# LICL_Diff.net
KiCad netlist of a schematic drawn in EAGLE
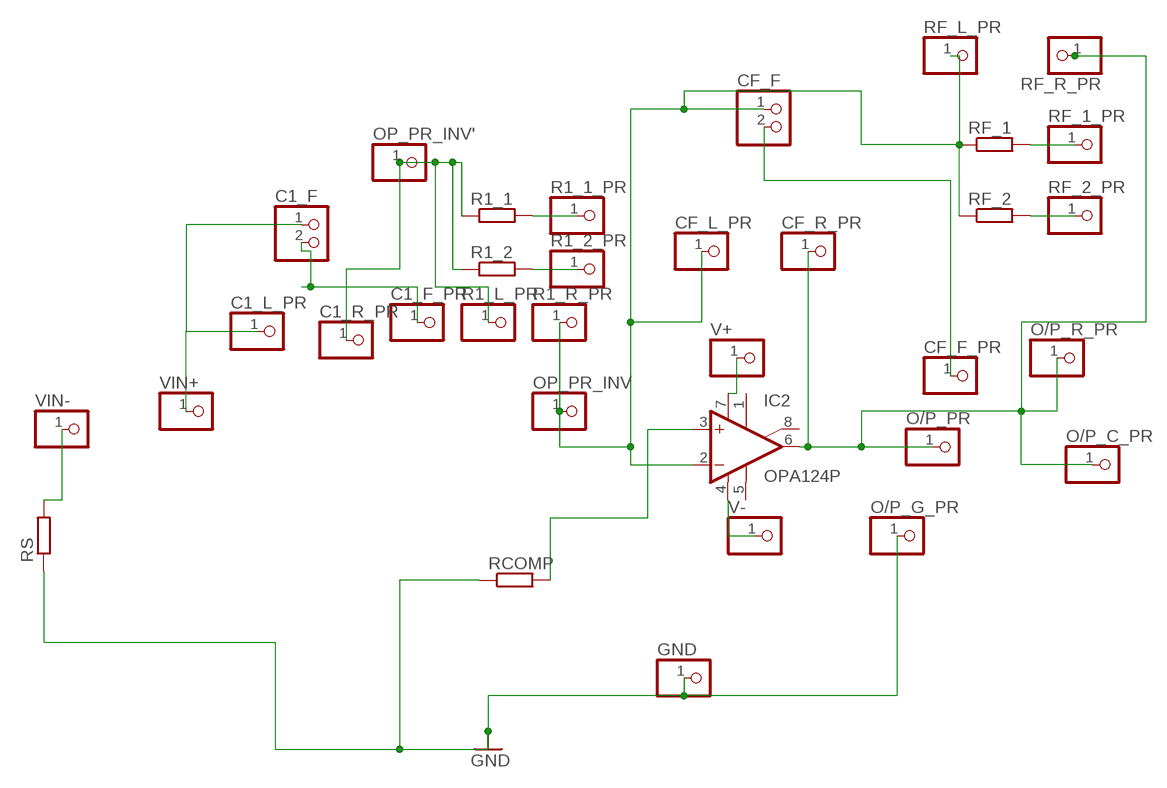
[diagram p0: schematic, sheet 1]

(export (version "E")
  (design (tool "Eeschema 10.0.6"))
  (components
    (comp (ref "C1_F")
      (value "PINHD-1X2")
      (footprint "eagle-import:1X02")
      (libsource (lib "eagle-import") (part "PINHD-1X2"))
    )
    (comp (ref "C1_F_PR")
      (value "PINHD-1X1")
      (footprint "eagle-import:1X01")
      (libsource (lib "eagle-import") (part "PINHD-1X1"))
    )
    (comp (ref "C1_L_PR")
      (value "PINHD-1X1")
      (footprint "eagle-import:1X01")
      (libsource (lib "eagle-import") (part "PINHD-1X1"))
    )
    (comp (ref "C1_R_PR")
      (value "PINHD-1X1")
      (footprint "eagle-import:1X01")
      (libsource (lib "eagle-import") (part "PINHD-1X1"))
    )
    (comp (ref "CF_F")
      (value "PINHD-1X2")
      (footprint "eagle-import:1X02")
      (libsource (lib "eagle-import") (part "PINHD-1X2"))
    )
    (comp (ref "CF_F_PR")
      (value "PINHD-1X1")
      (footprint "eagle-import:1X01")
      (libsource (lib "eagle-import") (part "PINHD-1X1"))
    )
    (comp (ref "CF_L_PR")
      (value "PINHD-1X1")
      (footprint "eagle-import:1X01")
      (libsource (lib "eagle-import") (part "PINHD-1X1"))
    )
    (comp (ref "CF_R_PR")
      (value "PINHD-1X1")
      (footprint "eagle-import:1X01")
      (libsource (lib "eagle-import") (part "PINHD-1X1"))
    )
    (comp (ref "GND")
      (value "PINHD-1X1")
      (footprint "eagle-import:1X01")
      (libsource (lib "eagle-import") (part "PINHD-1X1"))
    )
    (comp (ref "IC2")
      (value "OPA124P")
      (footprint "eagle-import:DIL08")
      (libsource (lib "eagle-import") (part "OPA124P"))
    )
    (comp (ref "O/P_C_PR")
      (value "PINHD-1X1")
      (footprint "eagle-import:1X01")
      (libsource (lib "eagle-import") (part "PINHD-1X1"))
    )
    (comp (ref "O/P_G_PR")
      (value "PINHD-1X1")
      (footprint "eagle-import:1X01")
      (libsource (lib "eagle-import") (part "PINHD-1X1"))
    )
    (comp (ref "O/P_PR")
      (value "PINHD-1X1")
      (footprint "eagle-import:1X01")
      (libsource (lib "eagle-import") (part "PINHD-1X1"))
    )
    (comp (ref "O/P_R_PR")
      (value "PINHD-1X1")
      (footprint "eagle-import:1X01")
      (libsource (lib "eagle-import") (part "PINHD-1X1"))
    )
    (comp (ref "OP_PR_INV")
      (value "PINHD-1X1")
      (footprint "eagle-import:1X01")
      (libsource (lib "eagle-import") (part "PINHD-1X1"))
    )
    (comp (ref "OP_PR_INV'")
      (value "PINHD-1X1")
      (footprint "eagle-import:1X01")
      (libsource (lib "eagle-import") (part "PINHD-1X1"))
    )
    (comp (ref "R1_1")
      (value "R-EU_0207/10")
      (footprint "eagle-import:0207_10")
      (libsource (lib "eagle-import") (part "R-EU_0207/10"))
    )
    (comp (ref "R1_1_PR")
      (value "PINHD-1X1")
      (footprint "eagle-import:1X01")
      (libsource (lib "eagle-import") (part "PINHD-1X1"))
    )
    (comp (ref "R1_2")
      (value "R-EU_0207/10")
      (footprint "eagle-import:0207_10")
      (libsource (lib "eagle-import") (part "R-EU_0207/10"))
    )
    (comp (ref "R1_2_PR")
      (value "PINHD-1X1")
      (footprint "eagle-import:1X01")
      (libsource (lib "eagle-import") (part "PINHD-1X1"))
    )
    (comp (ref "R1_L_PR")
      (value "PINHD-1X1")
      (footprint "eagle-import:1X01")
      (libsource (lib "eagle-import") (part "PINHD-1X1"))
    )
    (comp (ref "R1_R_PR")
      (value "PINHD-1X1")
      (footprint "eagle-import:1X01")
      (libsource (lib "eagle-import") (part "PINHD-1X1"))
    )
    (comp (ref "RCOMP")
      (value "R-EU_0207/10")
      (footprint "eagle-import:0207_10")
      (libsource (lib "eagle-import") (part "R-EU_0207/10"))
    )
    (comp (ref "RF_1")
      (value "R-EU_0207/10")
      (footprint "eagle-import:0207_10")
      (libsource (lib "eagle-import") (part "R-EU_0207/10"))
    )
    (comp (ref "RF_1_PR")
      (value "PINHD-1X1")
      (footprint "eagle-import:1X01")
      (libsource (lib "eagle-import") (part "PINHD-1X1"))
    )
    (comp (ref "RF_2")
      (value "R-EU_0207/10")
      (footprint "eagle-import:0207_10")
      (libsource (lib "eagle-import") (part "R-EU_0207/10"))
    )
    (comp (ref "RF_2_PR")
      (value "PINHD-1X1")
      (footprint "eagle-import:1X01")
      (libsource (lib "eagle-import") (part "PINHD-1X1"))
    )
    (comp (ref "RF_L_PR")
      (value "PINHD-1X1")
      (footprint "eagle-import:1X01")
      (libsource (lib "eagle-import") (part "PINHD-1X1"))
    )
    (comp (ref "RF_R_PR")
      (value "PINHD-1X1")
      (footprint "eagle-import:1X01")
      (libsource (lib "eagle-import") (part "PINHD-1X1"))
    )
    (comp (ref "RS")
      (value "R-EU_0207/10")
      (footprint "eagle-import:0207_10")
      (libsource (lib "eagle-import") (part "R-EU_0207/10"))
    )
    (comp (ref "V+")
      (value "PINHD-1X1")
      (footprint "eagle-import:1X01")
      (libsource (lib "eagle-import") (part "PINHD-1X1"))
    )
    (comp (ref "V-")
      (value "PINHD-1X1")
      (footprint "eagle-import:1X01")
      (libsource (lib "eagle-import") (part "PINHD-1X1"))
    )
    (comp (ref "VIN+")
      (value "PINHD-1X1")
      (footprint "eagle-import:1X01")
      (libsource (lib "eagle-import") (part "PINHD-1X1"))
    )
    (comp (ref "VIN-")
      (value "PINHD-1X1")
      (footprint "eagle-import:1X01")
      (libsource (lib "eagle-import") (part "PINHD-1X1"))
    )
  )
  (nets
    (net (code "1") (name "GND") (class "Default")
      (node (ref "GND") (pin "1") (pinfunction "1_1") (pintype "passive"))
      (node (ref "O/P_G_PR") (pin "1") (pinfunction "1_1") (pintype "passive"))
      (node (ref "RCOMP") (pin "1") (pinfunction "1_1") (pintype "passive"))
      (node (ref "RS") (pin "1") (pinfunction "1_1") (pintype "passive"))
    )
    (net (code "2") (name "Net-(C1_F-Pad1)") (class "Default")
      (node (ref "C1_F") (pin "1") (pinfunction "1_1") (pintype "passive"))
      (node (ref "C1_L_PR") (pin "1") (pinfunction "1_1") (pintype "passive"))
      (node (ref "VIN+") (pin "1") (pinfunction "1_1") (pintype "passive"))
    )
    (net (code "3") (name "Net-(C1_F-Pad2)") (class "Default")
      (node (ref "C1_F") (pin "2") (pinfunction "2_2") (pintype "passive"))
      (node (ref "C1_F_PR") (pin "1") (pinfunction "1_1") (pintype "passive"))
    )
    (net (code "4") (name "Net-(C1_R_PR-Pad1)") (class "Default")
      (node (ref "C1_R_PR") (pin "1") (pinfunction "1_1") (pintype "passive"))
      (node (ref "OP_PR_INV'") (pin "1") (pinfunction "1_1") (pintype "passive"))
      (node (ref "R1_1") (pin "1") (pinfunction "1_1") (pintype "passive"))
      (node (ref "R1_2") (pin "1") (pinfunction "1_1") (pintype "passive"))
      (node (ref "R1_L_PR") (pin "1") (pinfunction "1_1") (pintype "passive"))
    )
    (net (code "5") (name "Net-(CF_F-Pad2)") (class "Default")
      (node (ref "CF_F") (pin "2") (pinfunction "2_2") (pintype "passive"))
      (node (ref "CF_F_PR") (pin "1") (pinfunction "1_1") (pintype "passive"))
    )
    (net (code "6") (name "Net-(IC2-+IN)") (class "Default")
      (node (ref "IC2") (pin "3") (pinfunction "+IN_3") (pintype "input"))
      (node (ref "RCOMP") (pin "2") (pinfunction "2_2") (pintype "passive"))
    )
    (net (code "7") (name "Net-(IC2--IN)") (class "Default")
      (node (ref "CF_F") (pin "1") (pinfunction "1_1") (pintype "passive"))
      (node (ref "CF_L_PR") (pin "1") (pinfunction "1_1") (pintype "passive"))
      (node (ref "IC2") (pin "2") (pinfunction "-IN_2") (pintype "input"))
      (node (ref "OP_PR_INV") (pin "1") (pinfunction "1_1") (pintype "passive"))
      (node (ref "R1_R_PR") (pin "1") (pinfunction "1_1") (pintype "passive"))
      (node (ref "RF_1") (pin "1") (pinfunction "1_1") (pintype "passive"))
      (node (ref "RF_2") (pin "1") (pinfunction "1_1") (pintype "passive"))
      (node (ref "RF_L_PR") (pin "1") (pinfunction "1_1") (pintype "passive"))
    )
    (net (code "8") (name "Net-(IC2-OUT)") (class "Default")
      (node (ref "CF_R_PR") (pin "1") (pinfunction "1_1") (pintype "passive"))
      (node (ref "IC2") (pin "6") (pinfunction "OUT_6") (pintype "output"))
      (node (ref "O/P_C_PR") (pin "1") (pinfunction "1_1") (pintype "passive"))
      (node (ref "O/P_PR") (pin "1") (pinfunction "1_1") (pintype "passive"))
      (node (ref "O/P_R_PR") (pin "1") (pinfunction "1_1") (pintype "passive"))
      (node (ref "RF_R_PR") (pin "1") (pinfunction "1_1") (pintype "passive"))
    )
    (net (code "9") (name "Net-(IC2-V+)") (class "Default")
      (node (ref "IC2") (pin "7") (pinfunction "V+_7") (pintype "power_in"))
      (node (ref "V+") (pin "1") (pinfunction "1_1") (pintype "passive"))
    )
    (net (code "10") (name "Net-(IC2-V-)") (class "Default")
      (node (ref "IC2") (pin "4") (pinfunction "V-_4") (pintype "power_in"))
      (node (ref "V-") (pin "1") (pinfunction "1_1") (pintype "passive"))
    )
    (net (code "11") (name "Net-(R1_1-Pad2)") (class "Default")
      (node (ref "R1_1") (pin "2") (pinfunction "2_2") (pintype "passive"))
      (node (ref "R1_1_PR") (pin "1") (pinfunction "1_1") (pintype "passive"))
    )
    (net (code "12") (name "Net-(R1_2-Pad2)") (class "Default")
      (node (ref "R1_2") (pin "2") (pinfunction "2_2") (pintype "passive"))
      (node (ref "R1_2_PR") (pin "1") (pinfunction "1_1") (pintype "passive"))
    )
    (net (code "13") (name "Net-(RF_1-Pad2)") (class "Default")
      (node (ref "RF_1") (pin "2") (pinfunction "2_2") (pintype "passive"))
      (node (ref "RF_1_PR") (pin "1") (pinfunction "1_1") (pintype "passive"))
    )
    (net (code "14") (name "Net-(RF_2-Pad2)") (class "Default")
      (node (ref "RF_2") (pin "2") (pinfunction "2_2") (pintype "passive"))
      (node (ref "RF_2_PR") (pin "1") (pinfunction "1_1") (pintype "passive"))
    )
    (net (code "15") (name "Net-(RS-Pad2)") (class "Default")
      (node (ref "RS") (pin "2") (pinfunction "2_2") (pintype "passive"))
      (node (ref "VIN-") (pin "1") (pinfunction "1_1") (pintype "passive"))
    )
    (net (code "16") (name "unconnected-(IC2-SUBS-Pad8)") (class "Default")
      (node (ref "IC2") (pin "8") (pinfunction "SUBS_8") (pintype "passive"))
    )
    (net (code "17") (name "unconnected-(IC2-TRIM1-Pad1)") (class "Default")
      (node (ref "IC2") (pin "1") (pinfunction "TRIM1_1") (pintype "passive"))
    )
    (net (code "18") (name "unconnected-(IC2-TRIM2-Pad5)") (class "Default")
      (node (ref "IC2") (pin "5") (pinfunction "TRIM2_5") (pintype "passive"))
    )
  )
)
